# schematic.net
KiCad netlist of a schematic drawn in EAGLE
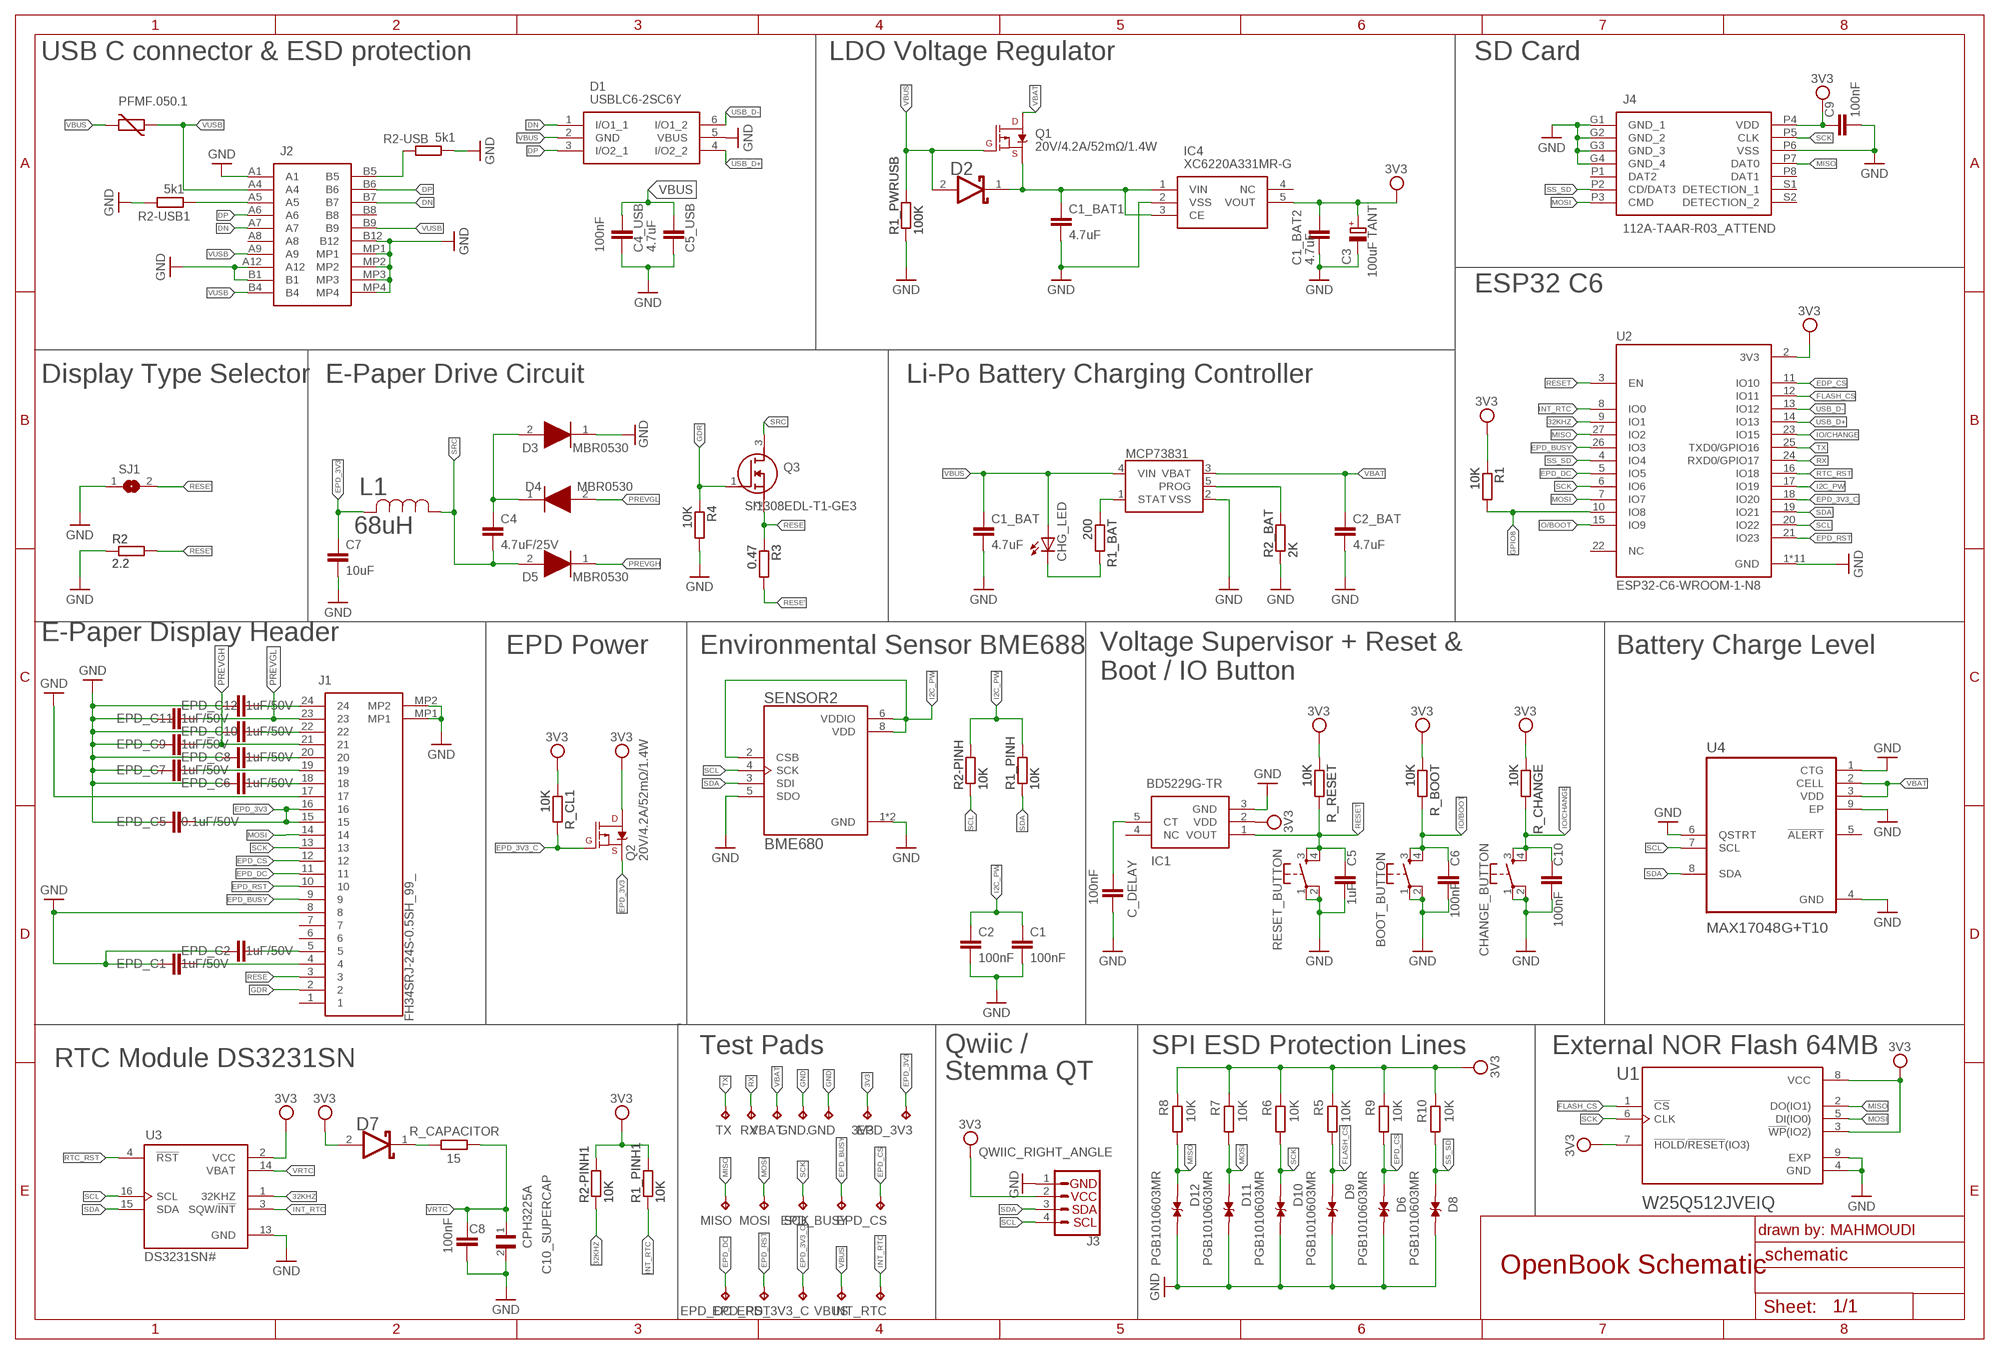
[diagram p0: schematic, sheet 1]

(export (version "E")
  (design (tool "Eeschema 10.0.6"))
  (components
    (comp (ref "3V3")
      (value "TPTP20R")
      (footprint "eagle-import:TP20R")
      (libsource (lib "eagle-import") (part "TPTP20R"))
    )
    (comp (ref "BOOT_BUTTON")
      (value "BUTTON_CUSYOMV1")
      (footprint "eagle-import:MYBUTTON")
      (libsource (lib "eagle-import") (part "BUTTON_CUSYOMV1"))
    )
    (comp (ref "C1")
      (value "100nF")
      (footprint "eagle-import:ESP32_WROVER_EAGLE-LTSPICE_C0402")
      (libsource (lib "eagle-import") (part "ESP32_WROVER_EAGLE-LTSPICE_CC0402"))
    )
    (comp (ref "C1_BAT")
      (value "4.7uF")
      (footprint "eagle-import:ESP32_WROVER_EAGLE-LTSPICE_C0402")
      (libsource (lib "eagle-import") (part "ESP32_WROVER_EAGLE-LTSPICE_CC0402"))
    )
    (comp (ref "C1_BAT1")
      (value "4.7uF")
      (footprint "eagle-import:EAGLE-LTSPICE_C0402")
      (libsource (lib "eagle-import") (part "EAGLE-LTSPICE_CC0402"))
    )
    (comp (ref "C1_BAT2")
      (value "4.7uF")
      (footprint "eagle-import:EAGLE-LTSPICE_C0402")
      (libsource (lib "eagle-import") (part "EAGLE-LTSPICE_CC0402"))
    )
    (comp (ref "C2")
      (value "100nF")
      (footprint "eagle-import:ESP32_WROVER_EAGLE-LTSPICE_C0402")
      (libsource (lib "eagle-import") (part "ESP32_WROVER_EAGLE-LTSPICE_CC0402"))
    )
    (comp (ref "C2_BAT")
      (value "4.7uF")
      (footprint "eagle-import:ESP32_WROVER_EAGLE-LTSPICE_C0402")
      (libsource (lib "eagle-import") (part "ESP32_WROVER_EAGLE-LTSPICE_CC0402"))
    )
    (comp (ref "C3")
      (value "100uF TANT")
      (footprint "eagle-import:RCL_CT3528")
      (libsource (lib "eagle-import") (part "RCL_CPOL-EUCT3528"))
    )
    (comp (ref "C4")
      (value "4.7uF/25V")
      (footprint "eagle-import:ESP32_WROVER_EAGLE-LTSPICE_C0402")
      (libsource (lib "eagle-import") (part "ESP32_WROVER_EAGLE-LTSPICE_CC0402"))
    )
    (comp (ref "C4_USB")
      (value "100nF")
      (footprint "eagle-import:EAGLE-LTSPICE_C0402")
      (libsource (lib "eagle-import") (part "EAGLE-LTSPICE_CC0402"))
    )
    (comp (ref "C5")
      (value "1uF")
      (footprint "eagle-import:ESP32_WROVER_EAGLE-LTSPICE_C0402")
      (libsource (lib "eagle-import") (part "ESP32_WROVER_EAGLE-LTSPICE_CC0402"))
    )
    (comp (ref "C5_USB")
      (value "4.7uF")
      (footprint "eagle-import:EAGLE-LTSPICE_C0402")
      (libsource (lib "eagle-import") (part "EAGLE-LTSPICE_CC0402"))
    )
    (comp (ref "C6")
      (value "100nF")
      (footprint "eagle-import:ESP32_WROVER_EAGLE-LTSPICE_C0402")
      (libsource (lib "eagle-import") (part "ESP32_WROVER_EAGLE-LTSPICE_CC0402"))
    )
    (comp (ref "C7")
      (value "10uF")
      (footprint "eagle-import:ESP32_WROVER_EAGLE-LTSPICE_C0402")
      (libsource (lib "eagle-import") (part "ESP32_WROVER_EAGLE-LTSPICE_CC0402"))
    )
    (comp (ref "C8")
      (value "100nF")
      (footprint "eagle-import:ESP32_WROVER_EAGLE-LTSPICE_C0402")
      (libsource (lib "eagle-import") (part "ESP32_WROVER_EAGLE-LTSPICE_CC0402"))
    )
    (comp (ref "C9")
      (value "100nF")
      (footprint "eagle-import:ESP32_WROVER_EAGLE-LTSPICE_C0402")
      (libsource (lib "eagle-import") (part "ESP32_WROVER_EAGLE-LTSPICE_CC0402"))
    )
    (comp (ref "C10")
      (value "100nF")
      (footprint "eagle-import:ESP32_WROVER_EAGLE-LTSPICE_C0402")
      (libsource (lib "eagle-import") (part "ESP32_WROVER_EAGLE-LTSPICE_CC0402"))
    )
    (comp (ref "C10_SUPERCAP")
      (value "CPH3225A")
      (footprint "eagle-import:CAPCP3225X100N")
      (fields (field (name "MF") "Seiko Instruments"))
      (libsource (lib "eagle-import") (part "CPH3225A"))
    )
    (comp (ref "CHANGE_BUTTON")
      (value "BUTTON_CUSYOMV1")
      (footprint "eagle-import:MYBUTTON")
      (libsource (lib "eagle-import") (part "BUTTON_CUSYOMV1"))
    )
    (comp (ref "CHG_LED")
      (value "ADAFRUIT_LEDCHIP-LED0603")
      (footprint "eagle-import:ADAFRUIT_CHIP-LED0603")
      (libsource (lib "eagle-import") (part "ADAFRUIT_LEDCHIP-LED0603"))
    )
    (comp (ref "C_DELAY")
      (value "100nF")
      (footprint "eagle-import:ESP32_WROVER_EAGLE-LTSPICE_C0402")
      (libsource (lib "eagle-import") (part "ESP32_WROVER_EAGLE-LTSPICE_CC0402"))
    )
    (comp (ref "D1")
      (value "USBLC6-2SC6Y")
      (footprint "eagle-import:SOT95P280X145-6N")
      (fields (field (name "MF") "STMicroelectronics"))
      (libsource (lib "eagle-import") (part "USBLC6-2SC6Y"))
    )
    (comp (ref "D2")
      (value "ESP32_WROVER_AVX---SD0805S020S1R0_AVX_SD0805S020S1R0_0_0AVX_SD0805S020S1R0_0_0")
      (footprint "eagle-import:ESP32_WROVER_AVX---SD0805S020S1R0_AVX_SD0805S020S1R0_0")
      (fields
        (field (name "DIGIKEY_PART_NUMBER") "478-7800-1-ND")
        (field (name "MF") "AVX")
        (field (name "MOUSER_PART_NUMBER") "581-SD0805S020S1R0")
      )
      (libsource (lib "eagle-import") (part "ESP32_WROVER_AVX---SD0805S020S1R0_AVX_SD0805S020S1R0_0_0AVX_SD0805S020S1R0_0_0"))
    )
    (comp (ref "D3")
      (value "MBR0530")
      (footprint "eagle-import:SOD3716X135N")
      (fields (field (name "MF") "ON Semiconductor"))
      (libsource (lib "eagle-import") (part "MBR0530"))
    )
    (comp (ref "D4")
      (value "MBR0530")
      (footprint "eagle-import:SOD3716X135N")
      (fields (field (name "MF") "ON Semiconductor"))
      (libsource (lib "eagle-import") (part "MBR0530"))
    )
    (comp (ref "D5")
      (value "MBR0530")
      (footprint "eagle-import:SOD3716X135N")
      (fields (field (name "MF") "ON Semiconductor"))
      (libsource (lib "eagle-import") (part "MBR0530"))
    )
    (comp (ref "D6")
      (value "PGB1010603MR")
      (footprint "eagle-import:DIOC1608X36N")
      (fields (field (name "MF") "Littelfuse Inc."))
      (libsource (lib "eagle-import") (part "PGB1010603MR"))
    )
    (comp (ref "D7")
      (value "SD0805S020S1R0")
      (footprint "eagle-import:ESP32_WROVER_AVX---SD0805S020S1R0_AVX_SD0805S020S1R0_0")
      (fields
        (field (name "DIGIKEY_PART_NUMBER") "478-7800-1-ND")
        (field (name "MF") "AVX")
        (field (name "MOUSER_PART_NUMBER") "581-SD0805S020S1R0")
      )
      (libsource (lib "eagle-import") (part "ESP32_WROVER_AVX---SD0805S020S1R0_AVX_SD0805S020S1R0_0_0AVX_SD0805S020S1R0_0_0"))
    )
    (comp (ref "D8")
      (value "PGB1010603MR")
      (footprint "eagle-import:DIOC1608X36N")
      (fields (field (name "MF") "Littelfuse Inc."))
      (libsource (lib "eagle-import") (part "PGB1010603MR"))
    )
    (comp (ref "D9")
      (value "PGB1010603MR")
      (footprint "eagle-import:DIOC1608X36N")
      (fields (field (name "MF") "Littelfuse Inc."))
      (libsource (lib "eagle-import") (part "PGB1010603MR"))
    )
    (comp (ref "D10")
      (value "PGB1010603MR")
      (footprint "eagle-import:DIOC1608X36N")
      (fields (field (name "MF") "Littelfuse Inc."))
      (libsource (lib "eagle-import") (part "PGB1010603MR"))
    )
    (comp (ref "D11")
      (value "PGB1010603MR")
      (footprint "eagle-import:DIOC1608X36N")
      (fields (field (name "MF") "Littelfuse Inc."))
      (libsource (lib "eagle-import") (part "PGB1010603MR"))
    )
    (comp (ref "D12")
      (value "PGB1010603MR")
      (footprint "eagle-import:DIOC1608X36N")
      (fields (field (name "MF") "Littelfuse Inc."))
      (libsource (lib "eagle-import") (part "PGB1010603MR"))
    )
    (comp (ref "EPD_3V3")
      (value "TPTP20R")
      (footprint "eagle-import:TP20R")
      (libsource (lib "eagle-import") (part "TPTP20R"))
    )
    (comp (ref "EPD_3V3_C")
      (value "TPTP20R")
      (footprint "eagle-import:TP20R")
      (libsource (lib "eagle-import") (part "TPTP20R"))
    )
    (comp (ref "EPD_BUSY")
      (value "TPTP20R")
      (footprint "eagle-import:TP20R")
      (libsource (lib "eagle-import") (part "TPTP20R"))
    )
    (comp (ref "EPD_C1")
      (value "1uF/50V")
      (footprint "eagle-import:ESP32_WROVER_EAGLE-LTSPICE_C0402")
      (libsource (lib "eagle-import") (part "ESP32_WROVER_EAGLE-LTSPICE_CC0402"))
    )
    (comp (ref "EPD_C2")
      (value "1uF/50V")
      (footprint "eagle-import:ESP32_WROVER_EAGLE-LTSPICE_C0402")
      (libsource (lib "eagle-import") (part "ESP32_WROVER_EAGLE-LTSPICE_CC0402"))
    )
    (comp (ref "EPD_C5")
      (value "0.1uF/50V")
      (footprint "eagle-import:ESP32_WROVER_EAGLE-LTSPICE_C0402")
      (libsource (lib "eagle-import") (part "ESP32_WROVER_EAGLE-LTSPICE_CC0402"))
    )
    (comp (ref "EPD_C6")
      (value "1uF/50V")
      (footprint "eagle-import:ESP32_WROVER_EAGLE-LTSPICE_C0402")
      (libsource (lib "eagle-import") (part "ESP32_WROVER_EAGLE-LTSPICE_CC0402"))
    )
    (comp (ref "EPD_C7")
      (value "1uF/50V")
      (footprint "eagle-import:ESP32_WROVER_EAGLE-LTSPICE_C0402")
      (libsource (lib "eagle-import") (part "ESP32_WROVER_EAGLE-LTSPICE_CC0402"))
    )
    (comp (ref "EPD_C8")
      (value "1uF/50V")
      (footprint "eagle-import:ESP32_WROVER_EAGLE-LTSPICE_C0402")
      (libsource (lib "eagle-import") (part "ESP32_WROVER_EAGLE-LTSPICE_CC0402"))
    )
    (comp (ref "EPD_C9")
      (value "1uF/50V")
      (footprint "eagle-import:ESP32_WROVER_EAGLE-LTSPICE_C0402")
      (libsource (lib "eagle-import") (part "ESP32_WROVER_EAGLE-LTSPICE_CC0402"))
    )
    (comp (ref "EPD_C10")
      (value "1uF/50V")
      (footprint "eagle-import:ESP32_WROVER_EAGLE-LTSPICE_C0402")
      (libsource (lib "eagle-import") (part "ESP32_WROVER_EAGLE-LTSPICE_CC0402"))
    )
    (comp (ref "EPD_C11")
      (value "1uF/50V")
      (footprint "eagle-import:ESP32_WROVER_EAGLE-LTSPICE_C0402")
      (libsource (lib "eagle-import") (part "ESP32_WROVER_EAGLE-LTSPICE_CC0402"))
    )
    (comp (ref "EPD_C12")
      (value "1uF/50V")
      (footprint "eagle-import:ESP32_WROVER_EAGLE-LTSPICE_C0402")
      (libsource (lib "eagle-import") (part "ESP32_WROVER_EAGLE-LTSPICE_CC0402"))
    )
    (comp (ref "EPD_CS")
      (value "TPTP20R")
      (footprint "eagle-import:TP20R")
      (libsource (lib "eagle-import") (part "TPTP20R"))
    )
    (comp (ref "EPD_DC")
      (value "TPTP20R")
      (footprint "eagle-import:TP20R")
      (libsource (lib "eagle-import") (part "TPTP20R"))
    )
    (comp (ref "EPD_RST")
      (value "TPTP20R")
      (footprint "eagle-import:TP20R")
      (libsource (lib "eagle-import") (part "TPTP20R"))
    )
    (comp (ref "GND")
      (value "TPTP20R")
      (footprint "eagle-import:TP20R")
      (libsource (lib "eagle-import") (part "TPTP20R"))
    )
    (comp (ref "GND.")
      (value "TPTP20R")
      (footprint "eagle-import:TP20R")
      (libsource (lib "eagle-import") (part "TPTP20R"))
    )
    (comp (ref "IC1")
      (value "BD5229G-TR")
      (footprint "eagle-import:SOT95P280X125-5N")
      (fields (field (name "MOUSER_PART_NUMBER") "755-BD5229G-TR"))
      (libsource (lib "eagle-import") (part "BD5229G-TR"))
    )
    (comp (ref "IC4")
      (value "XC6220A331MR-G")
      (footprint "eagle-import:SOT95P280X120-5N")
      (fields (field (name "MOUSER_PART_NUMBER") "865-XC6220A331MR-G"))
      (libsource (lib "eagle-import") (part "XC6220A331MR-G"))
    )
    (comp (ref "INT_RTC")
      (value "TPTP20R")
      (footprint "eagle-import:TP20R")
      (libsource (lib "eagle-import") (part "TPTP20R"))
    )
    (comp (ref "J1")
      (value "FH34SRJ-24S-0.5SH_99_")
      (footprint "eagle-import:FH34SRJ24S05SH99")
      (fields
        (field (name "MANUFACTURER_PART_NUMBER") "FH34SRJ-24S-0.5SH(99)")
        (field (name "MOUSER_PART_NUMBER") "798-FH34SRJ24S05SH99")
      )
      (libsource (lib "eagle-import") (part "FH34SRJ-24S-0.5SH_99_"))
    )
    (comp (ref "J2")
      (value "SAMACSYS_PARTS_USB4110-GF-A")
      (footprint "eagle-import:SAMACSYS_PARTS_USB4110GFA")
      (fields
        (field (name "MANUFACTURER_PART_NUMBER") "USB4110-GF-A")
        (field (name "MOUSER_PART_NUMBER") "640-USB4110-GF-A")
      )
      (libsource (lib "eagle-import") (part "SAMACSYS_PARTS_USB4110-GF-A"))
    )
    (comp (ref "J3")
      (value "QWIIC_RIGHT_ANGLE")
      (footprint "eagle-import:JST04_1MM_RA")
      (libsource (lib "eagle-import") (part "QWIIC_CONNECTORJS-1MM"))
    )
    (comp (ref "J4")
      (value "112A-TAAR-R03_ATTEND")
      (footprint "eagle-import:112ATAARR03ATTEND")
      (fields (field (name "MANUFACTURER_PART_NUMBER") "112A-TAAR-R03 ATTEND"))
      (libsource (lib "eagle-import") (part "112A-TAAR-R03_ATTEND"))
    )
    (comp (ref "L1")
      (value "68uH")
      (footprint "eagle-import:IND_4828-WE-TPC_WRE")
      (fields
        (field (name "MANUFACTURER_PART_NUMBER") "744043680")
        (field (name "COPYRIGHT") "Copyright (C) 2024 Ultra Librarian. All rights reserved.")
      )
      (libsource (lib "eagle-import") (part "744043680IND_4828-WE-TPC_WRE"))
    )
    (comp (ref "MCP73831")
      (value "ESP32_WROVER_SPARKFUN-IC-POWER_MCP73831")
      (footprint "eagle-import:ESP32_WROVER_SPARKFUN-IC-POWER_SOT23-5")
      (libsource (lib "eagle-import") (part "ESP32_WROVER_SPARKFUN-IC-POWER_MCP73831"))
    )
    (comp (ref "MISO")
      (value "TPTP20R")
      (footprint "eagle-import:TP20R")
      (libsource (lib "eagle-import") (part "TPTP20R"))
    )
    (comp (ref "MOSI")
      (value "TPTP20R")
      (footprint "eagle-import:TP20R")
      (libsource (lib "eagle-import") (part "TPTP20R"))
    )
    (comp (ref "PFMF.050.1")
      (value "ESP32C6_VARISTORCN1812")
      (footprint "eagle-import:ESP32C6_VARISTOR_CT_CN1812")
      (libsource (lib "eagle-import") (part "ESP32C6_VARISTORCN1812"))
    )
    (comp (ref "Q1")
      (value "20V/4.2A/52mΩ/1.4W")
      (footprint "eagle-import:ESP32_WROVER_SPARKFUN-DISCRETESEMI_SOT23-3")
      (libsource (lib "eagle-import") (part "ESP32_WROVER_SPARKFUN-DISCRETESEMI_MOSFET_PCH-DMG2305UX-7"))
    )
    (comp (ref "Q2")
      (value "20V/4.2A/52mΩ/1.4W")
      (footprint "eagle-import:ESP32_WROVER_SPARKFUN-DISCRETESEMI_SOT23-3")
      (libsource (lib "eagle-import") (part "ESP32_WROVER_SPARKFUN-DISCRETESEMI_MOSFET_PCH-DMG2305UX-7"))
    )
    (comp (ref "Q3")
      (value "SI1308EDL-T1-GE3")
      (footprint "eagle-import:SOT65P210X110-3N")
      (fields (field (name "MF") "Vishay Siliconix"))
      (libsource (lib "eagle-import") (part "SI1308EDL-T1-GE3"))
    )
    (comp (ref "R1")
      (value "10K")
      (footprint "eagle-import:ESP32_WROVER_EAGLE-LTSPICE_R0402")
      (libsource (lib "eagle-import") (part "ESP32_WROVER_EAGLE-LTSPICE_RR0402"))
    )
    (comp (ref "R1_BAT")
      (value "200")
      (footprint "eagle-import:ESP32_WROVER_EAGLE-LTSPICE_R0402")
      (libsource (lib "eagle-import") (part "ESP32_WROVER_EAGLE-LTSPICE_RR0402"))
    )
    (comp (ref "R1_PINH")
      (value "10K")
      (footprint "eagle-import:ESP32_WROVER_EAGLE-LTSPICE_R0402")
      (libsource (lib "eagle-import") (part "ESP32_WROVER_EAGLE-LTSPICE_RR0402"))
    )
    (comp (ref "R1_PINH1")
      (value "10K")
      (footprint "eagle-import:ESP32_WROVER_EAGLE-LTSPICE_R0402")
      (libsource (lib "eagle-import") (part "ESP32_WROVER_EAGLE-LTSPICE_RR0402"))
    )
    (comp (ref "R1_PWRUSB")
      (value "100K")
      (footprint "eagle-import:ESP32_WROVER_EAGLE-LTSPICE_R0402")
      (libsource (lib "eagle-import") (part "ESP32_WROVER_EAGLE-LTSPICE_RR0402"))
    )
    (comp (ref "R2")
      (value "2.2")
      (footprint "eagle-import:ESP32_WROVER_EAGLE-LTSPICE_R0402")
      (libsource (lib "eagle-import") (part "ESP32_WROVER_EAGLE-LTSPICE_RR0402"))
    )
    (comp (ref "R2-PINH")
      (value "10K")
      (footprint "eagle-import:ESP32_WROVER_EAGLE-LTSPICE_R0402")
      (libsource (lib "eagle-import") (part "ESP32_WROVER_EAGLE-LTSPICE_RR0402"))
    )
    (comp (ref "R2-PINH1")
      (value "10K")
      (footprint "eagle-import:ESP32_WROVER_EAGLE-LTSPICE_R0402")
      (libsource (lib "eagle-import") (part "ESP32_WROVER_EAGLE-LTSPICE_RR0402"))
    )
    (comp (ref "R2-USB")
      (value "5k1")
      (footprint "eagle-import:ESP32_WROVER_EAGLE-LTSPICE_R0402")
      (libsource (lib "eagle-import") (part "ESP32_WROVER_EAGLE-LTSPICE_RR0402"))
    )
    (comp (ref "R2-USB1")
      (value "5k1")
      (footprint "eagle-import:ESP32_WROVER_EAGLE-LTSPICE_R0402")
      (libsource (lib "eagle-import") (part "ESP32_WROVER_EAGLE-LTSPICE_RR0402"))
    )
    (comp (ref "R2_BAT")
      (value "2K")
      (footprint "eagle-import:ESP32_WROVER_EAGLE-LTSPICE_R0402")
      (libsource (lib "eagle-import") (part "ESP32_WROVER_EAGLE-LTSPICE_RR0402"))
    )
    (comp (ref "R3")
      (value "0.47")
      (footprint "eagle-import:ESP32_WROVER_EAGLE-LTSPICE_R0402")
      (libsource (lib "eagle-import") (part "ESP32_WROVER_EAGLE-LTSPICE_RR0402"))
    )
    (comp (ref "R4")
      (value "10K")
      (footprint "eagle-import:ESP32_WROVER_EAGLE-LTSPICE_R0402")
      (libsource (lib "eagle-import") (part "ESP32_WROVER_EAGLE-LTSPICE_RR0402"))
    )
    (comp (ref "R5")
      (value "10K")
      (footprint "eagle-import:ESP32_WROVER_EAGLE-LTSPICE_R0402")
      (libsource (lib "eagle-import") (part "ESP32_WROVER_EAGLE-LTSPICE_RR0402"))
    )
    (comp (ref "R6")
      (value "10K")
      (footprint "eagle-import:ESP32_WROVER_EAGLE-LTSPICE_R0402")
      (libsource (lib "eagle-import") (part "ESP32_WROVER_EAGLE-LTSPICE_RR0402"))
    )
    (comp (ref "R7")
      (value "10K")
      (footprint "eagle-import:ESP32_WROVER_EAGLE-LTSPICE_R0402")
      (libsource (lib "eagle-import") (part "ESP32_WROVER_EAGLE-LTSPICE_RR0402"))
    )
    (comp (ref "R8")
      (value "10K")
      (footprint "eagle-import:ESP32_WROVER_EAGLE-LTSPICE_R0402")
      (libsource (lib "eagle-import") (part "ESP32_WROVER_EAGLE-LTSPICE_RR0402"))
    )
    (comp (ref "R9")
      (value "10K")
      (footprint "eagle-import:ESP32_WROVER_EAGLE-LTSPICE_R0402")
      (libsource (lib "eagle-import") (part "ESP32_WROVER_EAGLE-LTSPICE_RR0402"))
    )
    (comp (ref "R10")
      (value "10K")
      (footprint "eagle-import:ESP32_WROVER_EAGLE-LTSPICE_R0402")
      (libsource (lib "eagle-import") (part "ESP32_WROVER_EAGLE-LTSPICE_RR0402"))
    )
    (comp (ref "RESET_BUTTON")
      (value "RESET_BUTTON")
      (footprint "eagle-import:MYBUTTON")
      (libsource (lib "eagle-import") (part "BUTTON_CUSYOMV1"))
    )
    (comp (ref "RX")
      (value "TPTP20R")
      (footprint "eagle-import:TP20R")
      (libsource (lib "eagle-import") (part "TPTP20R"))
    )
    (comp (ref "R_BOOT")
      (value "10K")
      (footprint "eagle-import:ESP32_WROVER_EAGLE-LTSPICE_R0402")
      (libsource (lib "eagle-import") (part "ESP32_WROVER_EAGLE-LTSPICE_RR0402"))
    )
    (comp (ref "R_CAPACITOR")
      (value "15")
      (footprint "eagle-import:ESP32_WROVER_EAGLE-LTSPICE_R0402")
      (libsource (lib "eagle-import") (part "ESP32_WROVER_EAGLE-LTSPICE_RR0402"))
    )
    (comp (ref "R_CHANGE")
      (value "10K")
      (footprint "eagle-import:ESP32_WROVER_EAGLE-LTSPICE_R0402")
      (libsource (lib "eagle-import") (part "ESP32_WROVER_EAGLE-LTSPICE_RR0402"))
    )
    (comp (ref "R_CL1")
      (value "10K")
      (footprint "eagle-import:ESP32_WROVER_EAGLE-LTSPICE_R0402")
      (libsource (lib "eagle-import") (part "ESP32_WROVER_EAGLE-LTSPICE_RR0402"))
    )
    (comp (ref "R_RESET")
      (value "10K")
      (footprint "eagle-import:ESP32_WROVER_EAGLE-LTSPICE_R0402")
      (libsource (lib "eagle-import") (part "ESP32_WROVER_EAGLE-LTSPICE_RR0402"))
    )
    (comp (ref "SCK")
      (value "TPTP20R")
      (footprint "eagle-import:TP20R")
      (libsource (lib "eagle-import") (part "TPTP20R"))
    )
    (comp (ref "SENSOR2")
      (value "BME680")
      (footprint "eagle-import:ESP32_WROVER_BME680_PSON80P300X300X100-8N")
      (fields (field (name "MF") "Bosch Sensortec"))
      (libsource (lib "eagle-import") (part "ESP32_WROVER_BME680_BME680"))
    )
    (comp (ref "SJ1") (value "SJ") (footprint "eagle-import:SJ") (libsource (lib "eagle-import") (part "SJ")))
    (comp (ref "TX")
      (value "TPTP20R")
      (footprint "eagle-import:TP20R")
      (libsource (lib "eagle-import") (part "TPTP20R"))
    )
    (comp (ref "U1")
      (value "W25Q512JVEIQ")
      (footprint "eagle-import:SON127P600X800X80-9N")
      (fields (field (name "MF") "Winbond Electronics"))
      (libsource (lib "eagle-import") (part "W25Q512JVEIQ"))
    )
    (comp (ref "U2")
      (value "ESP32-C6-WROOM-1-N8")
      (footprint "eagle-import:XCVR_ESP32-C6-WROOM-1-N8")
      (fields (field (name "MF") "Espressif Systems"))
      (libsource (lib "eagle-import") (part "ESP32-C6-WROOM-1-N8"))
    )
    (comp (ref "U3")
      (value "DS3231SN#")
      (footprint "eagle-import:SOIC127P1032X265-16N")
      (fields (field (name "MF") "Analog Devices"))
      (libsource (lib "eagle-import") (part "DS3231SN#"))
    )
    (comp (ref "U4")
      (value "MAX17048G+T10")
      (footprint "eagle-import:SON50P200X200X80-9N")
      (fields (field (name "MF") "Analog Devices"))
      (libsource (lib "eagle-import") (part "MAX17048G+T10"))
    )
    (comp (ref "VBAT")
      (value "TPTP20R")
      (footprint "eagle-import:TP20R")
      (libsource (lib "eagle-import") (part "TPTP20R"))
    )
    (comp (ref "VBUS")
      (value "TPTP20R")
      (footprint "eagle-import:TP20R")
      (libsource (lib "eagle-import") (part "TPTP20R"))
    )
  )
  (nets
    (net (code "1") (name "3V3") (class "Default")
      (node (ref "3V3") (pin "TP") (pinfunction "TP_TP") (pintype "input"))
      (node (ref "C1_BAT2") (pin "1") (pinfunction "1_1") (pintype "passive"))
      (node (ref "C3") (pin "+") (pinfunction "+_+") (pintype "passive"))
      (node (ref "C9") (pin "1") (pinfunction "1_1") (pintype "passive"))
      (node (ref "D7") (pin "2") (pinfunction "ANODE_2") (pintype "bidirectional"))
      (node (ref "IC1") (pin "2") (pinfunction "VDD_2") (pintype "bidirectional"))
      (node (ref "IC4") (pin "5") (pinfunction "VOUT_5") (pintype "bidirectional"))
      (node (ref "J3") (pin "2") (pinfunction "2_2") (pintype "power_in"))
      (node (ref "J4") (pin "P4") (pinfunction "VDD_P4") (pintype "bidirectional"))
      (node (ref "Q2") (pin "3") (pinfunction "D_3") (pintype "bidirectional"))
      (node (ref "R1") (pin "1") (pinfunction "1_1") (pintype "passive"))
      (node (ref "R10") (pin "1") (pinfunction "1_1") (pintype "passive"))
      (node (ref "R1_PINH1") (pin "2") (pinfunction "2_2") (pintype "passive"))
      (node (ref "R2-PINH1") (pin "2") (pinfunction "2_2") (pintype "passive"))
      (node (ref "R5") (pin "1") (pinfunction "1_1") (pintype "passive"))
      (node (ref "R6") (pin "1") (pinfunction "1_1") (pintype "passive"))
      (node (ref "R7") (pin "1") (pinfunction "1_1") (pintype "passive"))
      (node (ref "R8") (pin "1") (pinfunction "1_1") (pintype "passive"))
      (node (ref "R9") (pin "1") (pinfunction "1_1") (pintype "passive"))
      (node (ref "R_BOOT") (pin "1") (pinfunction "1_1") (pintype "passive"))
      (node (ref "R_CHANGE") (pin "1") (pinfunction "1_1") (pintype "passive"))
      (node (ref "R_CL1") (pin "1") (pinfunction "1_1") (pintype "passive"))
      (node (ref "R_RESET") (pin "1") (pinfunction "1_1") (pintype "passive"))
      (node (ref "U1") (pin "3") (pinfunction "~{WP}(IO2)_3") (pintype "bidirectional"))
      (node (ref "U1") (pin "7") (pinfunction "~{HOLD}/~{RESET}(IO3)_7") (pintype "bidirectional"))
      (node (ref "U1") (pin "8") (pinfunction "VCC_8") (pintype "power_in"))
      (node (ref "U2") (pin "2") (pinfunction "3V3_2") (pintype "power_in"))
      (node (ref "U3") (pin "2") (pinfunction "VCC_2") (pintype "power_in"))
    )
    (net (code "2") (name "32KHZ") (class "Default")
      (node (ref "R2-PINH1") (pin "1") (pinfunction "1_1") (pintype "passive"))
      (node (ref "U2") (pin "9") (pinfunction "IO1_9") (pintype "bidirectional"))
      (node (ref "U3") (pin "1") (pinfunction "32KHZ_1") (pintype "output"))
    )
    (net (code "3") (name "DN") (class "Default")
      (node (ref "D1") (pin "1") (pinfunction "I/O1_1_1") (pintype "bidirectional"))
      (node (ref "J2") (pin "A7") (pinfunction "A7_A7") (pintype "bidirectional"))
      (node (ref "J2") (pin "B7") (pinfunction "B7_B7") (pintype "bidirectional"))
    )
    (net (code "4") (name "DP") (class "Default")
      (node (ref "D1") (pin "3") (pinfunction "I/O2_1_3") (pintype "bidirectional"))
      (node (ref "J2") (pin "A6") (pinfunction "A6_A6") (pintype "bidirectional"))
      (node (ref "J2") (pin "B6") (pinfunction "B6_B6") (pintype "bidirectional"))
    )
    (net (code "5") (name "EDP_CS") (class "Default")
      (node (ref "U2") (pin "11") (pinfunction "IO10_11") (pintype "bidirectional"))
    )
    (net (code "6") (name "EPD_3V3") (class "Default")
      (node (ref "C7") (pin "1") (pinfunction "1_1") (pintype "passive"))
      (node (ref "EPD_3V3") (pin "TP") (pinfunction "TP_TP") (pintype "input"))
      (node (ref "EPD_C5") (pin "2") (pinfunction "2_2") (pintype "passive"))
      (node (ref "J1") (pin "15") (pinfunction "15_15") (pintype "bidirectional"))
      (node (ref "J1") (pin "16") (pinfunction "16_16") (pintype "bidirectional"))
      (node (ref "L1") (pin "2") (pinfunction "2_2") (pintype "passive"))
      (node (ref "Q2") (pin "2") (pinfunction "S_2") (pintype "bidirectional"))
    )
    (net (code "7") (name "EPD_3V3_C") (class "Default")
      (node (ref "EPD_3V3_C") (pin "TP") (pinfunction "TP_TP") (pintype "input"))
      (node (ref "Q2") (pin "1") (pinfunction "G_1") (pintype "bidirectional"))
      (node (ref "R_CL1") (pin "2") (pinfunction "2_2") (pintype "passive"))
      (node (ref "U2") (pin "18") (pinfunction "IO20_18") (pintype "bidirectional"))
    )
    (net (code "8") (name "EPD_BUSY") (class "Default")
      (node (ref "EPD_BUSY") (pin "TP") (pinfunction "TP_TP") (pintype "input"))
      (node (ref "J1") (pin "9") (pinfunction "9_9") (pintype "bidirectional"))
      (node (ref "U2") (pin "26") (pinfunction "IO3_26") (pintype "bidirectional"))
    )
    (net (code "9") (name "EPD_CS") (class "Default")
      (node (ref "D6") (pin "1") (pinfunction "1_1") (pintype "passive"))
      (node (ref "EPD_CS") (pin "TP") (pinfunction "TP_TP") (pintype "input"))
      (node (ref "J1") (pin "12") (pinfunction "12_12") (pintype "bidirectional"))
      (node (ref "R9") (pin "2") (pinfunction "2_2") (pintype "passive"))
    )
    (net (code "10") (name "EPD_DC") (class "Default")
      (node (ref "EPD_DC") (pin "TP") (pinfunction "TP_TP") (pintype "input"))
      (node (ref "J1") (pin "11") (pinfunction "11_11") (pintype "bidirectional"))
      (node (ref "U2") (pin "5") (pinfunction "IO5_5") (pintype "bidirectional"))
    )
    (net (code "11") (name "EPD_RST") (class "Default")
      (node (ref "EPD_RST") (pin "TP") (pinfunction "TP_TP") (pintype "input"))
      (node (ref "J1") (pin "10") (pinfunction "10_10") (pintype "bidirectional"))
      (node (ref "U2") (pin "21") (pinfunction "IO23_21") (pintype "bidirectional"))
    )
    (net (code "12") (name "FLASH_CS") (class "Default")
      (node (ref "D9") (pin "1") (pinfunction "1_1") (pintype "passive"))
      (node (ref "R5") (pin "2") (pinfunction "2_2") (pintype "passive"))
      (node (ref "U1") (pin "1") (pinfunction "~{CS}_1") (pintype "input"))
      (node (ref "U2") (pin "12") (pinfunction "IO11_12") (pintype "bidirectional"))
    )
    (net (code "13") (name "GDR") (class "Default")
      (node (ref "J1") (pin "2") (pinfunction "2_2") (pintype "bidirectional"))
      (node (ref "Q3") (pin "1") (pinfunction "G_1") (pintype "bidirectional"))
      (node (ref "R4") (pin "1") (pinfunction "1_1") (pintype "passive"))
    )
    (net (code "14") (name "GND") (class "Default")
      (node (ref "BOOT_BUTTON") (pin "1") (pinfunction "1_1") (pintype "passive"))
      (node (ref "BOOT_BUTTON") (pin "2") (pinfunction "2_2") (pintype "passive"))
      (node (ref "C1") (pin "2") (pinfunction "2_2") (pintype "passive"))
      (node (ref "C10") (pin "2") (pinfunction "2_2") (pintype "passive"))
      (node (ref "C10_SUPERCAP") (pin "2") (pinfunction "2_2") (pintype "passive"))
      (node (ref "C1_BAT") (pin "2") (pinfunction "2_2") (pintype "passive"))
      (node (ref "C1_BAT1") (pin "2") (pinfunction "2_2") (pintype "passive"))
      (node (ref "C1_BAT2") (pin "2") (pinfunction "2_2") (pintype "passive"))
      (node (ref "C2") (pin "2") (pinfunction "2_2") (pintype "passive"))
      (node (ref "C2_BAT") (pin "2") (pinfunction "2_2") (pintype "passive"))
      (node (ref "C3") (pin "-") (pinfunction "-_-") (pintype "passive"))
      (node (ref "C4_USB") (pin "2") (pinfunction "2_2") (pintype "passive"))
      (node (ref "C5") (pin "2") (pinfunction "2_2") (pintype "passive"))
      (node (ref "C5_USB") (pin "2") (pinfunction "2_2") (pintype "passive"))
      (node (ref "C6") (pin "2") (pinfunction "2_2") (pintype "passive"))
      (node (ref "C7") (pin "2") (pinfunction "2_2") (pintype "passive"))
      (node (ref "C8") (pin "2") (pinfunction "2_2") (pintype "passive"))
      (node (ref "C9") (pin "2") (pinfunction "2_2") (pintype "passive"))
      (node (ref "CHANGE_BUTTON") (pin "1") (pinfunction "1_1") (pintype "passive"))
      (node (ref "CHANGE_BUTTON") (pin "2") (pinfunction "2_2") (pintype "passive"))
      (node (ref "C_DELAY") (pin "2") (pinfunction "2_2") (pintype "passive"))
      (node (ref "D1") (pin "5") (pinfunction "VBUS_5") (pintype "bidirectional"))
      (node (ref "D10") (pin "2") (pinfunction "2_2") (pintype "passive"))
      (node (ref "D11") (pin "2") (pinfunction "2_2") (pintype "passive"))
      (node (ref "D12") (pin "2") (pinfunction "2_2") (pintype "passive"))
      (node (ref "D3") (pin "1") (pinfunction "K_1") (pintype "bidirectional"))
      (node (ref "D6") (pin "2") (pinfunction "2_2") (pintype "passive"))
      (node (ref "D8") (pin "2") (pinfunction "2_2") (pintype "passive"))
      (node (ref "D9") (pin "2") (pinfunction "2_2") (pintype "passive"))
      (node (ref "EPD_C1") (pin "1") (pinfunction "1_1") (pintype "passive"))
      (node (ref "EPD_C10") (pin "1") (pinfunction "1_1") (pintype "passive"))
      (node (ref "EPD_C11") (pin "1") (pinfunction "1_1") (pintype "passive"))
      (node (ref "EPD_C12") (pin "1") (pinfunction "1_1") (pintype "passive"))
      (node (ref "EPD_C2") (pin "1") (pinfunction "1_1") (pintype "passive"))
      (node (ref "EPD_C5") (pin "1") (pinfunction "1_1") (pintype "passive"))
      (node (ref "EPD_C6") (pin "1") (pinfunction "1_1") (pintype "passive"))
      (node (ref "EPD_C7") (pin "1") (pinfunction "1_1") (pintype "passive"))
      (node (ref "EPD_C8") (pin "1") (pinfunction "1_1") (pintype "passive"))
      (node (ref "EPD_C9") (pin "1") (pinfunction "1_1") (pintype "passive"))
      (node (ref "GND") (pin "TP") (pinfunction "TP_TP") (pintype "input"))
      (node (ref "GND.") (pin "TP") (pinfunction "TP_TP") (pintype "input"))
      (node (ref "IC1") (pin "3") (pinfunction "GND_3") (pintype "bidirectional"))
      (node (ref "IC4") (pin "2") (pinfunction "VSS_2") (pintype "bidirectional"))
      (node (ref "J1") (pin "17") (pinfunction "17_17") (pintype "bidirectional"))
      (node (ref "J1") (pin "8") (pinfunction "8_8") (pintype "bidirectional"))
      (node (ref "J1") (pin "MP1") (pinfunction "MP1_MP1") (pintype "bidirectional"))
      (node (ref "J1") (pin "MP2") (pinfunction "MP2_MP2") (pintype "bidirectional"))
      (node (ref "J2") (pin "A1") (pinfunction "A1_A1") (pintype "bidirectional"))
      (node (ref "J2") (pin "A12") (pinfunction "A12_A12") (pintype "bidirectional"))
      (node (ref "J2") (pin "B1") (pinfunction "B1_B1") (pintype "bidirectional"))
      (node (ref "J2") (pin "B12") (pinfunction "B12_B12") (pintype "bidirectional"))
      (node (ref "J2") (pin "MP1") (pinfunction "MP1_MP1") (pintype "bidirectional"))
      (node (ref "J2") (pin "MP2") (pinfunction "MP2_MP2") (pintype "bidirectional"))
      (node (ref "J2") (pin "MP3") (pinfunction "MP3_MP3") (pintype "bidirectional"))
      (node (ref "J2") (pin "MP4") (pinfunction "MP4_MP4") (pintype "bidirectional"))
      (node (ref "J3") (pin "1") (pinfunction "1_1") (pintype "power_in"))
      (node (ref "J4") (pin "G1") (pinfunction "GND_1_G1") (pintype "bidirectional"))
      (node (ref "J4") (pin "G2") (pinfunction "GND_2_G2") (pintype "bidirectional"))
      (node (ref "J4") (pin "G3") (pinfunction "GND_3_G3") (pintype "bidirectional"))
      (node (ref "J4") (pin "G4") (pinfunction "GND_4_G4") (pintype "bidirectional"))
      (node (ref "J4") (pin "P6") (pinfunction "VSS_P6") (pintype "bidirectional"))
      (node (ref "MCP73831") (pin "2") (pinfunction "VSS_2") (pintype "power_in"))
      (node (ref "R1_PWRUSB") (pin "1") (pinfunction "1_1") (pintype "passive"))
      (node (ref "R2") (pin "1") (pinfunction "1_1") (pintype "passive"))
      (node (ref "R2-USB") (pin "2") (pinfunction "2_2") (pintype "passive"))
      (node (ref "R2-USB1") (pin "1") (pinfunction "1_1") (pintype "passive"))
      (node (ref "R2_BAT") (pin "1") (pinfunction "1_1") (pintype "passive"))
      (node (ref "R4") (pin "2") (pinfunction "2_2") (pintype "passive"))
      (node (ref "RESET_BUTTON") (pin "1") (pinfunction "1_1") (pintype "passive"))
      (node (ref "RESET_BUTTON") (pin "2") (pinfunction "2_2") (pintype "passive"))
      (node (ref "SENSOR2") (pin "1") (pinfunction "GND_1") (pintype "power_in"))
      (node (ref "SENSOR2") (pin "5") (pinfunction "SDO_5") (pintype "bidirectional"))
      (node (ref "SENSOR2") (pin "7") (pinfunction "GND_7") (pintype "power_in"))
      (node (ref "SJ1") (pin "1") (pinfunction "1_1") (pintype "passive"))
      (node (ref "U1") (pin "4") (pinfunction "GND_4") (pintype "power_in"))
      (node (ref "U1") (pin "9") (pinfunction "EXP_9") (pintype "passive"))
      (node (ref "U2") (pin "1") (pinfunction "GND_1") (pintype "power_in"))
      (node (ref "U2") (pin "28") (pinfunction "GND_28") (pintype "power_in"))
      (node (ref "U2") (pin "29_1") (pinfunction "GND_29_1") (pintype "power_in"))
      (node (ref "U2") (pin "29_2") (pinfunction "GND_29_2") (pintype "power_in"))
      (node (ref "U2") (pin "29_3") (pinfunction "GND_29_3") (pintype "power_in"))
      (node (ref "U2") (pin "29_4") (pinfunction "GND_29_4") (pintype "power_in"))
      (node (ref "U2") (pin "29_5") (pinfunction "GND_29_5") (pintype "power_in"))
      (node (ref "U2") (pin "29_6") (pinfunction "GND_29_6") (pintype "power_in"))
      (node (ref "U2") (pin "29_7") (pinfunction "GND_29_7") (pintype "power_in"))
      (node (ref "U2") (pin "29_8") (pinfunction "GND_29_8") (pintype "power_in"))
      (node (ref "U2") (pin "29_9") (pinfunction "GND_29_9") (pintype "power_in"))
      (node (ref "U3") (pin "13") (pinfunction "GND_13") (pintype "power_in"))
      (node (ref "U4") (pin "1") (pinfunction "CTG_1") (pintype "power_in"))
      (node (ref "U4") (pin "4") (pinfunction "GND_4") (pintype "power_in"))
      (node (ref "U4") (pin "6") (pinfunction "QSTRT_6") (pintype "input"))
      (node (ref "U4") (pin "9") (pinfunction "EP_9") (pintype "power_in"))
    )
    (net (code "15") (name "GPIO8") (class "Default")
      (node (ref "R1") (pin "2") (pinfunction "2_2") (pintype "passive"))
      (node (ref "U2") (pin "10") (pinfunction "IO8_10") (pintype "bidirectional"))
    )
    (net (code "16") (name "I2C_PW") (class "Default")
      (node (ref "C1") (pin "1") (pinfunction "1_1") (pintype "passive"))
      (node (ref "C2") (pin "1") (pinfunction "1_1") (pintype "passive"))
      (node (ref "R1_PINH") (pin "2") (pinfunction "2_2") (pintype "passive"))
      (node (ref "R2-PINH") (pin "2") (pinfunction "2_2") (pintype "passive"))
      (node (ref "SENSOR2") (pin "2") (pinfunction "CSB_2") (pintype "input"))
      (node (ref "SENSOR2") (pin "6") (pinfunction "VDDIO_6") (pintype "power_in"))
      (node (ref "SENSOR2") (pin "8") (pinfunction "VDD_8") (pintype "power_in"))
      (node (ref "U2") (pin "17") (pinfunction "IO19_17") (pintype "bidirectional"))
    )
    (net (code "17") (name "INT_RTC") (class "Default")
      (node (ref "INT_RTC") (pin "TP") (pinfunction "TP_TP") (pintype "input"))
      (node (ref "R1_PINH1") (pin "1") (pinfunction "1_1") (pintype "passive"))
      (node (ref "U2") (pin "8") (pinfunction "IO0_8") (pintype "bidirectional"))
      (node (ref "U3") (pin "3") (pinfunction "SQW/~{INT}_3") (pintype "output"))
    )
    (net (code "18") (name "IO{slash}BOOT") (class "Default")
      (node (ref "BOOT_BUTTON") (pin "3") (pinfunction "3_3") (pintype "passive"))
      (node (ref "BOOT_BUTTON") (pin "4") (pinfunction "4_4") (pintype "passive"))
      (node (ref "C6") (pin "1") (pinfunction "1_1") (pintype "passive"))
      (node (ref "R_BOOT") (pin "2") (pinfunction "2_2") (pintype "passive"))
      (node (ref "U2") (pin "15") (pinfunction "IO9_15") (pintype "bidirectional"))
    )
    (net (code "19") (name "IO{slash}CHANGE") (class "Default")
      (node (ref "C10") (pin "1") (pinfunction "1_1") (pintype "passive"))
      (node (ref "CHANGE_BUTTON") (pin "3") (pinfunction "3_3") (pintype "passive"))
      (node (ref "CHANGE_BUTTON") (pin "4") (pinfunction "4_4") (pintype "passive"))
      (node (ref "R_CHANGE") (pin "2") (pinfunction "2_2") (pintype "passive"))
      (node (ref "U2") (pin "23") (pinfunction "IO15_23") (pintype "bidirectional"))
    )
    (net (code "20") (name "MISO") (class "Default")
      (node (ref "D12") (pin "1") (pinfunction "1_1") (pintype "passive"))
      (node (ref "J4") (pin "P7") (pinfunction "DAT0_P7") (pintype "bidirectional"))
      (node (ref "MISO") (pin "TP") (pinfunction "TP_TP") (pintype "input"))
      (node (ref "R8") (pin "2") (pinfunction "2_2") (pintype "passive"))
      (node (ref "U1") (pin "2") (pinfunction "DO(IO1)_2") (pintype "bidirectional"))
      (node (ref "U2") (pin "27") (pinfunction "IO2_27") (pintype "bidirectional"))
    )
    (net (code "21") (name "MOSI") (class "Default")
      (node (ref "D11") (pin "1") (pinfunction "1_1") (pintype "passive"))
      (node (ref "J1") (pin "14") (pinfunction "14_14") (pintype "bidirectional"))
      (node (ref "J4") (pin "P3") (pinfunction "CMD_P3") (pintype "bidirectional"))
      (node (ref "MOSI") (pin "TP") (pinfunction "TP_TP") (pintype "input"))
      (node (ref "R7") (pin "2") (pinfunction "2_2") (pintype "passive"))
      (node (ref "U1") (pin "5") (pinfunction "DI(IO0)_5") (pintype "bidirectional"))
      (node (ref "U2") (pin "7") (pinfunction "IO7_7") (pintype "bidirectional"))
    )
    (net (code "22") (name "Net-(CHG_LED-PadC)") (class "Default")
      (node (ref "CHG_LED") (pin "C") (pinfunction "C_C") (pintype "passive"))
      (node (ref "R1_BAT") (pin "2") (pinfunction "2_2") (pintype "passive"))
    )
    (net (code "23") (name "Net-(D2-CATHODE)") (class "Default")
      (node (ref "C1_BAT1") (pin "1") (pinfunction "1_1") (pintype "passive"))
      (node (ref "D2") (pin "1") (pinfunction "CATHODE_1") (pintype "bidirectional"))
      (node (ref "IC4") (pin "1") (pinfunction "VIN_1") (pintype "bidirectional"))
      (node (ref "IC4") (pin "3") (pinfunction "CE_3") (pintype "bidirectional"))
      (node (ref "Q1") (pin "2") (pinfunction "S_2") (pintype "bidirectional"))
    )
    (net (code "24") (name "Net-(D3-A)") (class "Default")
      (node (ref "C4") (pin "1") (pinfunction "1_1") (pintype "passive"))
      (node (ref "D3") (pin "2") (pinfunction "A_2") (pintype "bidirectional"))
      (node (ref "D4") (pin "1") (pinfunction "K_1") (pintype "bidirectional"))
    )
    (net (code "25") (name "Net-(D7-CATHODE)") (class "Default")
      (node (ref "D7") (pin "1") (pinfunction "CATHODE_1") (pintype "bidirectional"))
      (node (ref "R_CAPACITOR") (pin "2") (pinfunction "2_2") (pintype "passive"))
    )
    (net (code "26") (name "Net-(EPD_C1-Pad2)") (class "Default")
      (node (ref "EPD_C1") (pin "2") (pinfunction "2_2") (pintype "passive"))
      (node (ref "J1") (pin "4") (pinfunction "4_4") (pintype "bidirectional"))
    )
    (net (code "27") (name "Net-(EPD_C2-Pad2)") (class "Default")
      (node (ref "EPD_C2") (pin "2") (pinfunction "2_2") (pintype "passive"))
      (node (ref "J1") (pin "5") (pinfunction "5_5") (pintype "bidirectional"))
    )
    (net (code "28") (name "Net-(EPD_C6-Pad2)") (class "Default")
      (node (ref "EPD_C6") (pin "2") (pinfunction "2_2") (pintype "passive"))
      (node (ref "J1") (pin "18") (pinfunction "18_18") (pintype "bidirectional"))
    )
    (net (code "29") (name "Net-(EPD_C7-Pad2)") (class "Default")
      (node (ref "EPD_C7") (pin "2") (pinfunction "2_2") (pintype "passive"))
      (node (ref "J1") (pin "19") (pinfunction "19_19") (pintype "bidirectional"))
    )
    (net (code "30") (name "Net-(EPD_C8-Pad2)") (class "Default")
      (node (ref "EPD_C8") (pin "2") (pinfunction "2_2") (pintype "passive"))
      (node (ref "J1") (pin "20") (pinfunction "20_20") (pintype "bidirectional"))
    )
    (net (code "31") (name "Net-(EPD_C10-Pad2)") (class "Default")
      (node (ref "EPD_C10") (pin "2") (pinfunction "2_2") (pintype "passive"))
      (node (ref "J1") (pin "22") (pinfunction "22_22") (pintype "bidirectional"))
    )
    (net (code "32") (name "Net-(EPD_C12-Pad2)") (class "Default")
      (node (ref "EPD_C12") (pin "2") (pinfunction "2_2") (pintype "passive"))
      (node (ref "J1") (pin "24") (pinfunction "24_24") (pintype "bidirectional"))
    )
    (net (code "33") (name "Net-(IC1-CT)") (class "Default")
      (node (ref "C_DELAY") (pin "1") (pinfunction "1_1") (pintype "passive"))
      (node (ref "IC1") (pin "5") (pinfunction "CT_5") (pintype "bidirectional"))
    )
    (net (code "34") (name "Net-(J2-PadA5)") (class "Default")
      (node (ref "J2") (pin "A5") (pinfunction "A5_A5") (pintype "bidirectional"))
      (node (ref "R2-USB1") (pin "2") (pinfunction "2_2") (pintype "passive"))
    )
    (net (code "35") (name "Net-(J2-PadB5)") (class "Default")
      (node (ref "J2") (pin "B5") (pinfunction "B5_B5") (pintype "bidirectional"))
      (node (ref "R2-USB") (pin "1") (pinfunction "1_1") (pintype "passive"))
    )
    (net (code "36") (name "Net-(MCP73831-PROG)") (class "Default")
      (node (ref "MCP73831") (pin "5") (pinfunction "PROG_5") (pintype "input"))
      (node (ref "R2_BAT") (pin "2") (pinfunction "2_2") (pintype "passive"))
    )
    (net (code "37") (name "Net-(MCP73831-STAT)") (class "Default")
      (node (ref "MCP73831") (pin "1") (pinfunction "STAT_1") (pintype "output"))
      (node (ref "R1_BAT") (pin "1") (pinfunction "1_1") (pintype "passive"))
    )
    (net (code "38") (name "PREVGH") (class "Default")
      (node (ref "D5") (pin "1") (pinfunction "K_1") (pintype "bidirectional"))
      (node (ref "EPD_C9") (pin "2") (pinfunction "2_2") (pintype "passive"))
      (node (ref "J1") (pin "21") (pinfunction "21_21") (pintype "bidirectional"))
    )
    (net (code "39") (name "PREVGL") (class "Default")
      (node (ref "D4") (pin "2") (pinfunction "A_2") (pintype "bidirectional"))
      (node (ref "EPD_C11") (pin "2") (pinfunction "2_2") (pintype "passive"))
      (node (ref "J1") (pin "23") (pinfunction "23_23") (pintype "bidirectional"))
    )
    (net (code "40") (name "RESE") (class "Default")
      (node (ref "J1") (pin "3") (pinfunction "3_3") (pintype "bidirectional"))
      (node (ref "Q3") (pin "2") (pinfunction "S_2") (pintype "bidirectional"))
      (node (ref "R3") (pin "1") (pinfunction "1_1") (pintype "passive"))
    )
    (net (code "41") (name "RESE'") (class "Default")
      (node (ref "R2") (pin "2") (pinfunction "2_2") (pintype "passive"))
      (node (ref "R3") (pin "2") (pinfunction "2_2") (pintype "passive"))
      (node (ref "SJ1") (pin "2") (pinfunction "2_2") (pintype "passive"))
    )
    (net (code "42") (name "RESET") (class "Default")
      (node (ref "C5") (pin "1") (pinfunction "1_1") (pintype "passive"))
      (node (ref "IC1") (pin "1") (pinfunction "VOUT_1") (pintype "bidirectional"))
      (node (ref "RESET_BUTTON") (pin "3") (pinfunction "3_3") (pintype "passive"))
      (node (ref "RESET_BUTTON") (pin "4") (pinfunction "4_4") (pintype "passive"))
      (node (ref "R_RESET") (pin "2") (pinfunction "2_2") (pintype "passive"))
      (node (ref "U2") (pin "3") (pinfunction "EN_3") (pintype "input"))
    )
    (net (code "43") (name "RTC_RST") (class "Default")
      (node (ref "U2") (pin "16") (pinfunction "IO18_16") (pintype "bidirectional"))
      (node (ref "U3") (pin "4") (pinfunction "~{RST}_4") (pintype "input"))
    )
    (net (code "44") (name "RX") (class "Default")
      (node (ref "RX") (pin "TP") (pinfunction "TP_TP") (pintype "input"))
      (node (ref "U2") (pin "24") (pinfunction "RXD0/GPIO17_24") (pintype "bidirectional"))
    )
    (net (code "45") (name "SCK") (class "Default")
      (node (ref "D10") (pin "1") (pinfunction "1_1") (pintype "passive"))
      (node (ref "J1") (pin "13") (pinfunction "13_13") (pintype "bidirectional"))
      (node (ref "J4") (pin "P5") (pinfunction "CLK_P5") (pintype "bidirectional"))
      (node (ref "R6") (pin "2") (pinfunction "2_2") (pintype "passive"))
      (node (ref "SCK") (pin "TP") (pinfunction "TP_TP") (pintype "input"))
      (node (ref "U1") (pin "6") (pinfunction "CLK_6") (pintype "input"))
      (node (ref "U2") (pin "6") (pinfunction "IO6_6") (pintype "bidirectional"))
    )
    (net (code "46") (name "SCL") (class "Default")
      (node (ref "J3") (pin "4") (pinfunction "4_4") (pintype "passive"))
      (node (ref "R2-PINH") (pin "1") (pinfunction "1_1") (pintype "passive"))
      (node (ref "SENSOR2") (pin "4") (pinfunction "SCK_4") (pintype "input"))
      (node (ref "U2") (pin "20") (pinfunction "IO22_20") (pintype "bidirectional"))
      (node (ref "U3") (pin "16") (pinfunction "SCL_16") (pintype "input"))
      (node (ref "U4") (pin "7") (pinfunction "SCL_7") (pintype "input"))
    )
    (net (code "47") (name "SDA") (class "Default")
      (node (ref "J3") (pin "3") (pinfunction "3_3") (pintype "passive"))
      (node (ref "R1_PINH") (pin "1") (pinfunction "1_1") (pintype "passive"))
      (node (ref "SENSOR2") (pin "3") (pinfunction "SDI_3") (pintype "bidirectional"))
      (node (ref "U2") (pin "19") (pinfunction "IO21_19") (pintype "bidirectional"))
      (node (ref "U3") (pin "15") (pinfunction "SDA_15") (pintype "bidirectional"))
      (node (ref "U4") (pin "8") (pinfunction "SDA_8") (pintype "bidirectional"))
    )
    (net (code "48") (name "SRC") (class "Default")
      (node (ref "C4") (pin "2") (pinfunction "2_2") (pintype "passive"))
      (node (ref "D5") (pin "2") (pinfunction "A_2") (pintype "bidirectional"))
      (node (ref "L1") (pin "1") (pinfunction "1_1") (pintype "passive"))
      (node (ref "Q3") (pin "3") (pinfunction "D_3") (pintype "bidirectional"))
    )
    (net (code "49") (name "SS_SD") (class "Default")
      (node (ref "D8") (pin "1") (pinfunction "1_1") (pintype "passive"))
      (node (ref "J4") (pin "P2") (pinfunction "CD/DAT3_P2") (pintype "bidirectional"))
      (node (ref "R10") (pin "2") (pinfunction "2_2") (pintype "passive"))
      (node (ref "U2") (pin "4") (pinfunction "IO4_4") (pintype "bidirectional"))
    )
    (net (code "50") (name "TX") (class "Default")
      (node (ref "TX") (pin "TP") (pinfunction "TP_TP") (pintype "input"))
      (node (ref "U2") (pin "25") (pinfunction "TXD0/GPIO16_25") (pintype "bidirectional"))
    )
    (net (code "51") (name "USB_D+") (class "Default")
      (node (ref "D1") (pin "4") (pinfunction "I/O2_2_4") (pintype "bidirectional"))
      (node (ref "U2") (pin "14") (pinfunction "IO13_14") (pintype "bidirectional"))
    )
    (net (code "52") (name "USB_D-") (class "Default")
      (node (ref "D1") (pin "6") (pinfunction "I/O1_2_6") (pintype "bidirectional"))
      (node (ref "U2") (pin "13") (pinfunction "IO12_13") (pintype "bidirectional"))
    )
    (net (code "53") (name "VBAT") (class "Default")
      (node (ref "C2_BAT") (pin "1") (pinfunction "1_1") (pintype "passive"))
      (node (ref "MCP73831") (pin "3") (pinfunction "VBAT_3") (pintype "power_in"))
      (node (ref "Q1") (pin "3") (pinfunction "D_3") (pintype "bidirectional"))
      (node (ref "U4") (pin "2") (pinfunction "CELL_2") (pintype "power_in"))
      (node (ref "U4") (pin "3") (pinfunction "VDD_3") (pintype "power_in"))
      (node (ref "VBAT") (pin "TP") (pinfunction "TP_TP") (pintype "input"))
    )
    (net (code "54") (name "VBUS") (class "Default")
      (node (ref "C1_BAT") (pin "1") (pinfunction "1_1") (pintype "passive"))
      (node (ref "C4_USB") (pin "1") (pinfunction "1_1") (pintype "passive"))
      (node (ref "C5_USB") (pin "1") (pinfunction "1_1") (pintype "passive"))
      (node (ref "CHG_LED") (pin "A") (pinfunction "A_A") (pintype "passive"))
      (node (ref "D1") (pin "2") (pinfunction "GND_2") (pintype "bidirectional"))
      (node (ref "D2") (pin "2") (pinfunction "ANODE_2") (pintype "bidirectional"))
      (node (ref "MCP73831") (pin "4") (pinfunction "VIN_4") (pintype "power_in"))
      (node (ref "PFMF.050.1") (pin "2") (pinfunction "2_2") (pintype "passive"))
      (node (ref "Q1") (pin "1") (pinfunction "G_1") (pintype "bidirectional"))
      (node (ref "R1_PWRUSB") (pin "2") (pinfunction "2_2") (pintype "passive"))
      (node (ref "VBUS") (pin "TP") (pinfunction "TP_TP") (pintype "input"))
    )
    (net (code "55") (name "VRTC") (class "Default")
      (node (ref "C10_SUPERCAP") (pin "1") (pinfunction "1_1") (pintype "passive"))
      (node (ref "C8") (pin "1") (pinfunction "1_1") (pintype "passive"))
      (node (ref "R_CAPACITOR") (pin "1") (pinfunction "1_1") (pintype "passive"))
      (node (ref "U3") (pin "14") (pinfunction "VBAT_14") (pintype "power_in"))
    )
    (net (code "56") (name "VUSB") (class "Default")
      (node (ref "J2") (pin "A4") (pinfunction "A4_A4") (pintype "bidirectional"))
      (node (ref "J2") (pin "A9") (pinfunction "A9_A9") (pintype "bidirectional"))
      (node (ref "J2") (pin "B4") (pinfunction "B4_B4") (pintype "bidirectional"))
      (node (ref "J2") (pin "B9") (pinfunction "B9_B9") (pintype "bidirectional"))
      (node (ref "PFMF.050.1") (pin "1") (pinfunction "1_1") (pintype "passive"))
    )
    (net (code "57") (name "unconnected-(IC1-NC-Pad4)") (class "Default")
      (node (ref "IC1") (pin "4") (pinfunction "NC_4") (pintype "no_connect"))
    )
    (net (code "58") (name "unconnected-(IC4-NC-Pad4)") (class "Default")
      (node (ref "IC4") (pin "4") (pinfunction "NC_4") (pintype "no_connect"))
    )
    (net (code "59") (name "unconnected-(J1-Pad1)") (class "Default")
      (node (ref "J1") (pin "1") (pinfunction "1_1") (pintype "bidirectional"))
    )
    (net (code "60") (name "unconnected-(J1-Pad6)") (class "Default")
      (node (ref "J1") (pin "6") (pinfunction "6_6") (pintype "bidirectional"))
    )
    (net (code "61") (name "unconnected-(J1-Pad7)") (class "Default")
      (node (ref "J1") (pin "7") (pinfunction "7_7") (pintype "bidirectional"))
    )
    (net (code "62") (name "unconnected-(J2-PadA8)") (class "Default")
      (node (ref "J2") (pin "A8") (pinfunction "A8_A8") (pintype "bidirectional"))
    )
    (net (code "63") (name "unconnected-(J2-PadB8)") (class "Default")
      (node (ref "J2") (pin "B8") (pinfunction "B8_B8") (pintype "bidirectional"))
    )
    (net (code "64") (name "unconnected-(J4-DAT1-PadP8)") (class "Default")
      (node (ref "J4") (pin "P8") (pinfunction "DAT1_P8") (pintype "bidirectional"))
    )
    (net (code "65") (name "unconnected-(J4-DAT2-PadP1)") (class "Default")
      (node (ref "J4") (pin "P1") (pinfunction "DAT2_P1") (pintype "bidirectional"))
    )
    (net (code "66") (name "unconnected-(J4-DETECTION_1-PadS1)") (class "Default")
      (node (ref "J4") (pin "S1") (pinfunction "DETECTION_1_S1") (pintype "bidirectional"))
    )
    (net (code "67") (name "unconnected-(J4-DETECTION_2-PadS2)") (class "Default")
      (node (ref "J4") (pin "S2") (pinfunction "DETECTION_2_S2") (pintype "bidirectional"))
    )
    (net (code "68") (name "unconnected-(U2-NC-Pad22)") (class "Default")
      (node (ref "U2") (pin "22") (pinfunction "NC_22") (pintype "no_connect"))
    )
    (net (code "69") (name "unconnected-(U4-~{ALERT}-Pad5)") (class "Default")
      (node (ref "U4") (pin "5") (pinfunction "~{ALERT}_5") (pintype "output"))
    )
  )
)
